# Processor.net
KiCad netlist of a schematic drawn in Altium Designer
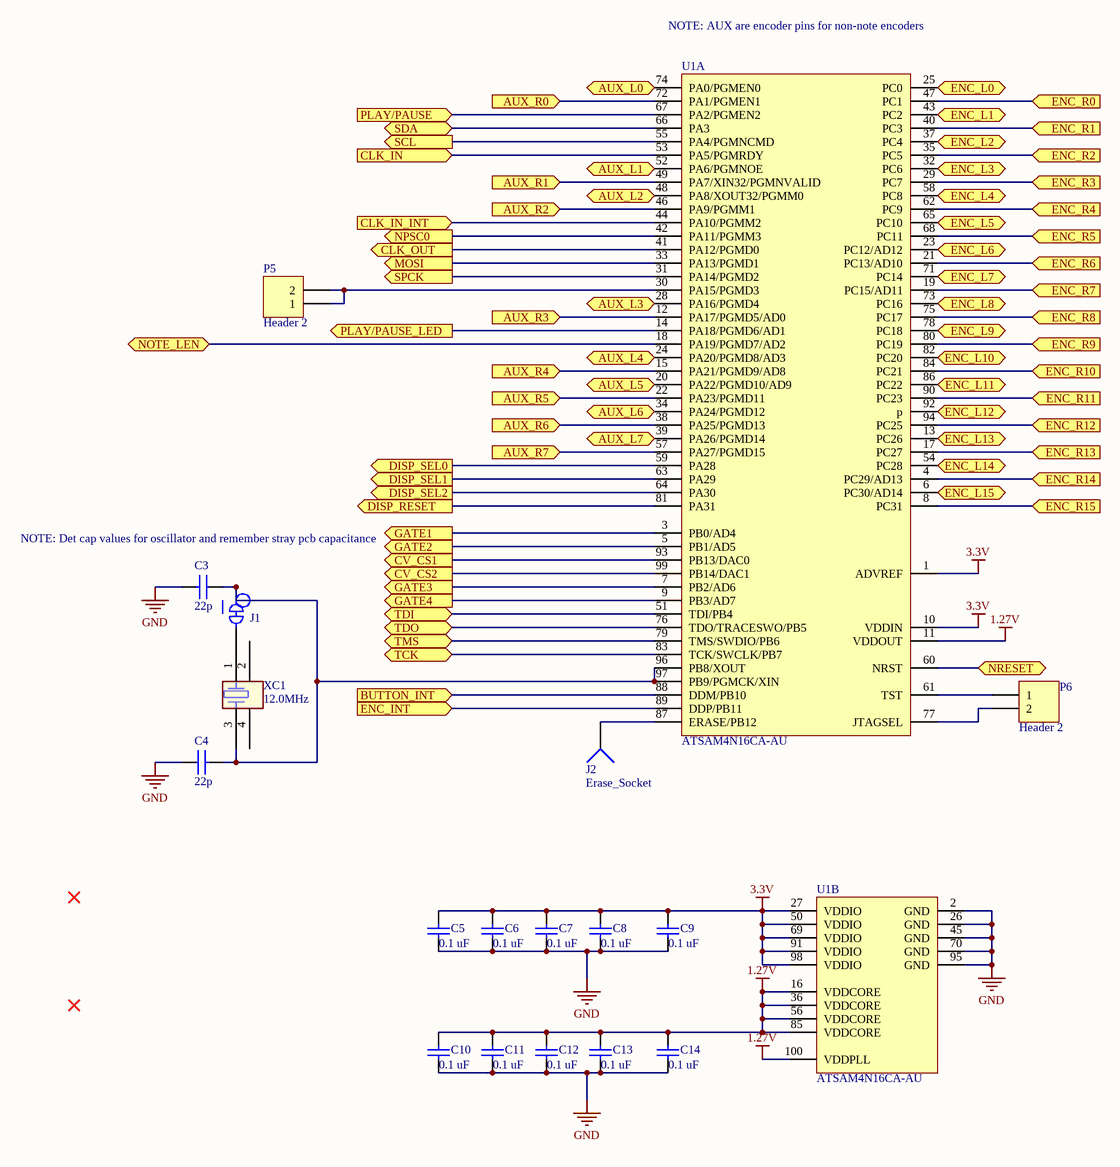
[diagram p0: Processor.SchDoc]

(export (version "E")
  (design (tool "Eeschema 10.0.6"))
  (components
    (comp (ref "C3")
      (value "22p")
      (footprint "AP1-00001")
      (description "Ceramic capacitor, SMD 0402, NP0, 50V, +/-5%")
      (fields (field (name "TOLERANCE") "50V, +/-5%") (field (name "Comment") "CAP-NONPOL"))
      (libsource (lib "AltiumDbLib") (part "CAP-NONPOL"))
    )
    (comp (ref "C4")
      (value "22p")
      (footprint "AP1-00001")
      (description "Ceramic capacitor, SMD 0402, NP0, 50V, +/-5%")
      (fields (field (name "TOLERANCE") "50V, +/-5%") (field (name "Comment") "CAP-NONPOL"))
      (libsource (lib "AltiumDbLib") (part "CAP-NONPOL"))
    )
    (comp (ref "C5")
      (value "0.1 uF")
      (footprint "C0805")
      (description "Capacitor")
      (fields (field (name "PUBLISHER") "Altium Limited"))
      (libsource (lib "Miscellaneous Devices") (part "Cap"))
    )
    (comp (ref "C6")
      (value "0.1 uF")
      (footprint "C0805")
      (description "Capacitor")
      (fields (field (name "PUBLISHER") "Altium Limited"))
      (libsource (lib "Miscellaneous Devices") (part "Cap"))
    )
    (comp (ref "C7")
      (value "0.1 uF")
      (footprint "C0805")
      (description "Capacitor")
      (fields (field (name "PUBLISHER") "Altium Limited"))
      (libsource (lib "Miscellaneous Devices") (part "Cap"))
    )
    (comp (ref "C8")
      (value "0.1 uF")
      (footprint "C0805")
      (description "Capacitor")
      (fields (field (name "PUBLISHER") "Altium Limited"))
      (libsource (lib "Miscellaneous Devices") (part "Cap"))
    )
    (comp (ref "C9")
      (value "0.1 uF")
      (footprint "C0805")
      (description "Capacitor")
      (fields (field (name "PUBLISHER") "Altium Limited"))
      (libsource (lib "Miscellaneous Devices") (part "Cap"))
    )
    (comp (ref "C10")
      (value "0.1 uF")
      (footprint "C0805")
      (description "Capacitor")
      (fields (field (name "PUBLISHER") "Altium Limited"))
      (libsource (lib "Miscellaneous Devices") (part "Cap"))
    )
    (comp (ref "C11")
      (value "0.1 uF")
      (footprint "C0805")
      (description "Capacitor")
      (fields (field (name "PUBLISHER") "Altium Limited"))
      (libsource (lib "Miscellaneous Devices") (part "Cap"))
    )
    (comp (ref "C12")
      (value "0.1 uF")
      (footprint "C0805")
      (description "Capacitor")
      (fields (field (name "PUBLISHER") "Altium Limited"))
      (libsource (lib "Miscellaneous Devices") (part "Cap"))
    )
    (comp (ref "C13")
      (value "0.1 uF")
      (footprint "C0805")
      (description "Capacitor")
      (fields (field (name "PUBLISHER") "Altium Limited"))
      (libsource (lib "Miscellaneous Devices") (part "Cap"))
    )
    (comp (ref "C14")
      (value "0.1 uF")
      (footprint "C0805")
      (description "Capacitor")
      (fields (field (name "PUBLISHER") "Altium Limited"))
      (libsource (lib "Miscellaneous Devices") (part "Cap"))
    )
    (comp (ref "J1")
      (value "SMD-STRAP_CLOSED")
      (footprint "AP9-00044")
      (description "Default closed SMD strap, 0603 size")
      (libsource (lib "AltiumDbLib") (part "SMD-STRAP_CLOSED"))
    )
    (comp (ref "J2")
      (value "Erase_Socket")
      (footprint "PIN1")
      (description "Socket")
      (fields (field (name "PUBLISHER") "Altium Limited"))
      (libsource (lib "Miscellaneous Connectors") (part "Socket"))
    )
    (comp (ref "P5")
      (value "Header 2")
      (footprint "HDR1X2")
      (description "Header, 2-Pin")
      (fields (field (name "PUBLISHER") "Altium Limited"))
      (libsource (lib "") (part "Header 2_1"))
    )
    (comp (ref "P6")
      (value "Header 2")
      (footprint "HDR1X2")
      (description "Header, 2-Pin")
      (fields (field (name "PUBLISHER") "Altium Limited"))
      (libsource (lib "Miscellaneous Connectors") (part "Header 2"))
    )
    (comp (ref "U1")
      (value "ATSAM4N16CA-AU")
      (footprint "LQFP100_N")
      (libsource (lib "Atmel Microcontroller ARM") (part "ATSAM4S16CA-AU"))
    )
    (comp (ref "XC1")
      (value "12.0MHz")
      (footprint "AP7-00039")
      (description "Fox FQ5032B 12.0MHz SMD crystal 738B-12")
      (fields (field (name "TOLERANCE") "30PPM") (field (name "MANUFACTURER") "Fox  Electronics"))
      (libsource (lib "AltiumDbLib") (part "CRYSTAL1324"))
    )
  )
  (nets
    (net (code "1") (name "/AUX_L0") (class "Default")
      (node (ref "U1") (pin "74") (pinfunction "PA0/PGMEN0_74") (pintype "passive"))
    )
    (net (code "2") (name "/AUX_L1") (class "Default")
      (node (ref "U1") (pin "52") (pinfunction "PA6/PGMNOE_52") (pintype "passive"))
    )
    (net (code "3") (name "/AUX_L2") (class "Default")
      (node (ref "U1") (pin "48") (pinfunction "PA8/XOUT32/PGMM0_48") (pintype "passive"))
    )
    (net (code "4") (name "/AUX_L3") (class "Default")
      (node (ref "U1") (pin "28") (pinfunction "PA16/PGMD4_28") (pintype "passive"))
    )
    (net (code "5") (name "/AUX_L4") (class "Default")
      (node (ref "U1") (pin "24") (pinfunction "PA20/PGMD8/AD3_24") (pintype "passive"))
    )
    (net (code "6") (name "/AUX_L5") (class "Default")
      (node (ref "U1") (pin "20") (pinfunction "PA22/PGMD10/AD9_20") (pintype "passive"))
    )
    (net (code "7") (name "/AUX_L6") (class "Default")
      (node (ref "U1") (pin "34") (pinfunction "PA24/PGMD12_34") (pintype "passive"))
    )
    (net (code "8") (name "/AUX_L7") (class "Default")
      (node (ref "U1") (pin "39") (pinfunction "PA26/PGMD14_39") (pintype "passive"))
    )
    (net (code "9") (name "/AUX_R0") (class "Default")
      (node (ref "U1") (pin "72") (pinfunction "PA1/PGMEN1_72") (pintype "passive"))
    )
    (net (code "10") (name "/AUX_R1") (class "Default")
      (node (ref "U1") (pin "49") (pinfunction "PA7/XIN32/PGMNVALID_49") (pintype "passive"))
    )
    (net (code "11") (name "/AUX_R2") (class "Default")
      (node (ref "U1") (pin "46") (pinfunction "PA9/PGMM1_46") (pintype "passive"))
    )
    (net (code "12") (name "/AUX_R3") (class "Default")
      (node (ref "U1") (pin "12") (pinfunction "PA17/PGMD5/AD0_12") (pintype "passive"))
    )
    (net (code "13") (name "/AUX_R4") (class "Default")
      (node (ref "U1") (pin "15") (pinfunction "PA21/PGMD9/AD8_15") (pintype "passive"))
    )
    (net (code "14") (name "/AUX_R5") (class "Default")
      (node (ref "U1") (pin "22") (pinfunction "PA23/PGMD11_22") (pintype "passive"))
    )
    (net (code "15") (name "/AUX_R6") (class "Default")
      (node (ref "U1") (pin "38") (pinfunction "PA25/PGMD13_38") (pintype "passive"))
    )
    (net (code "16") (name "/AUX_R7") (class "Default")
      (node (ref "U1") (pin "57") (pinfunction "PA27/PGMD15_57") (pintype "passive"))
    )
    (net (code "17") (name "/BUTTON_INT") (class "Default")
      (node (ref "U1") (pin "88") (pinfunction "DDM/PB10_88") (pintype "passive"))
    )
    (net (code "18") (name "/CLK_IN") (class "Default")
      (node (ref "U1") (pin "53") (pinfunction "PA5/PGMRDY_53") (pintype "passive"))
    )
    (net (code "19") (name "/CLK_IN_INT") (class "Default")
      (node (ref "U1") (pin "44") (pinfunction "PA10/PGMM2_44") (pintype "passive"))
    )
    (net (code "20") (name "/CLK_OUT") (class "Default")
      (node (ref "U1") (pin "41") (pinfunction "PA12/PGMD0_41") (pintype "passive"))
    )
    (net (code "21") (name "/CV_CS1") (class "Default")
      (node (ref "U1") (pin "93") (pinfunction "PB13/DAC0_93") (pintype "passive"))
    )
    (net (code "22") (name "/CV_CS2") (class "Default")
      (node (ref "U1") (pin "99") (pinfunction "PB14/DAC1_99") (pintype "passive"))
    )
    (net (code "23") (name "/DISP_RESET") (class "Default")
      (node (ref "U1") (pin "81") (pinfunction "PA31_81") (pintype "passive"))
    )
    (net (code "24") (name "/DISP_SEL0") (class "Default")
      (node (ref "U1") (pin "59") (pinfunction "PA28_59") (pintype "passive"))
    )
    (net (code "25") (name "/DISP_SEL1") (class "Default")
      (node (ref "U1") (pin "63") (pinfunction "PA29_63") (pintype "passive"))
    )
    (net (code "26") (name "/DISP_SEL2") (class "Default")
      (node (ref "U1") (pin "64") (pinfunction "PA30_64") (pintype "passive"))
    )
    (net (code "27") (name "/ENC_INT") (class "Default")
      (node (ref "U1") (pin "89") (pinfunction "DDP/PB11_89") (pintype "passive"))
    )
    (net (code "28") (name "/ENC_L0") (class "Default")
      (node (ref "U1") (pin "25") (pinfunction "PC0_25") (pintype "passive"))
    )
    (net (code "29") (name "/ENC_L1") (class "Default")
      (node (ref "U1") (pin "43") (pinfunction "PC2_43") (pintype "passive"))
    )
    (net (code "30") (name "/ENC_L2") (class "Default")
      (node (ref "U1") (pin "37") (pinfunction "PC4_37") (pintype "passive"))
    )
    (net (code "31") (name "/ENC_L3") (class "Default")
      (node (ref "U1") (pin "32") (pinfunction "PC6_32") (pintype "passive"))
    )
    (net (code "32") (name "/ENC_L4") (class "Default")
      (node (ref "U1") (pin "58") (pinfunction "PC8_58") (pintype "passive"))
    )
    (net (code "33") (name "/ENC_L5") (class "Default")
      (node (ref "U1") (pin "65") (pinfunction "PC10_65") (pintype "passive"))
    )
    (net (code "34") (name "/ENC_L6") (class "Default")
      (node (ref "U1") (pin "23") (pinfunction "PC12/AD12_23") (pintype "passive"))
    )
    (net (code "35") (name "/ENC_L7") (class "Default")
      (node (ref "U1") (pin "71") (pinfunction "PC14_71") (pintype "passive"))
    )
    (net (code "36") (name "/ENC_L8") (class "Default")
      (node (ref "U1") (pin "73") (pinfunction "PC16_73") (pintype "passive"))
    )
    (net (code "37") (name "/ENC_L9") (class "Default")
      (node (ref "U1") (pin "78") (pinfunction "PC18_78") (pintype "passive"))
    )
    (net (code "38") (name "/ENC_L10") (class "Default")
      (node (ref "U1") (pin "82") (pinfunction "PC20_82") (pintype "passive"))
    )
    (net (code "39") (name "/ENC_L11") (class "Default")
      (node (ref "U1") (pin "86") (pinfunction "PC22_86") (pintype "passive"))
    )
    (net (code "40") (name "/ENC_L12") (class "Default")
      (node (ref "U1") (pin "92") (pinfunction "p_92") (pintype "passive"))
    )
    (net (code "41") (name "/ENC_L13") (class "Default")
      (node (ref "U1") (pin "13") (pinfunction "PC26_13") (pintype "passive"))
    )
    (net (code "42") (name "/ENC_L14") (class "Default")
      (node (ref "U1") (pin "54") (pinfunction "PC28_54") (pintype "passive"))
    )
    (net (code "43") (name "/ENC_L15") (class "Default")
      (node (ref "U1") (pin "6") (pinfunction "PC30/AD14_6") (pintype "passive"))
    )
    (net (code "44") (name "/ENC_R0") (class "Default")
      (node (ref "U1") (pin "47") (pinfunction "PC1_47") (pintype "passive"))
    )
    (net (code "45") (name "/ENC_R1") (class "Default")
      (node (ref "U1") (pin "40") (pinfunction "PC3_40") (pintype "passive"))
    )
    (net (code "46") (name "/ENC_R2") (class "Default")
      (node (ref "U1") (pin "35") (pinfunction "PC5_35") (pintype "passive"))
    )
    (net (code "47") (name "/ENC_R3") (class "Default")
      (node (ref "U1") (pin "29") (pinfunction "PC7_29") (pintype "passive"))
    )
    (net (code "48") (name "/ENC_R4") (class "Default")
      (node (ref "U1") (pin "62") (pinfunction "PC9_62") (pintype "passive"))
    )
    (net (code "49") (name "/ENC_R5") (class "Default")
      (node (ref "U1") (pin "68") (pinfunction "PC11_68") (pintype "passive"))
    )
    (net (code "50") (name "/ENC_R6") (class "Default")
      (node (ref "U1") (pin "21") (pinfunction "PC13/AD10_21") (pintype "passive"))
    )
    (net (code "51") (name "/ENC_R7") (class "Default")
      (node (ref "U1") (pin "19") (pinfunction "PC15/AD11_19") (pintype "passive"))
    )
    (net (code "52") (name "/ENC_R8") (class "Default")
      (node (ref "U1") (pin "75") (pinfunction "PC17_75") (pintype "passive"))
    )
    (net (code "53") (name "/ENC_R9") (class "Default")
      (node (ref "U1") (pin "80") (pinfunction "PC19_80") (pintype "passive"))
    )
    (net (code "54") (name "/ENC_R10") (class "Default")
      (node (ref "U1") (pin "84") (pinfunction "PC21_84") (pintype "passive"))
    )
    (net (code "55") (name "/ENC_R11") (class "Default")
      (node (ref "U1") (pin "90") (pinfunction "PC23_90") (pintype "passive"))
    )
    (net (code "56") (name "/ENC_R12") (class "Default")
      (node (ref "U1") (pin "94") (pinfunction "PC25_94") (pintype "passive"))
    )
    (net (code "57") (name "/ENC_R13") (class "Default")
      (node (ref "U1") (pin "17") (pinfunction "PC27_17") (pintype "passive"))
    )
    (net (code "58") (name "/ENC_R14") (class "Default")
      (node (ref "U1") (pin "4") (pinfunction "PC29/AD13_4") (pintype "passive"))
    )
    (net (code "59") (name "/ENC_R15") (class "Default")
      (node (ref "U1") (pin "8") (pinfunction "PC31_8") (pintype "passive"))
    )
    (net (code "60") (name "/GATE1") (class "Default")
      (node (ref "U1") (pin "3") (pinfunction "PB0/AD4_3") (pintype "passive"))
    )
    (net (code "61") (name "/GATE2") (class "Default")
      (node (ref "U1") (pin "5") (pinfunction "PB1/AD5_5") (pintype "passive"))
    )
    (net (code "62") (name "/GATE3") (class "Default")
      (node (ref "U1") (pin "7") (pinfunction "PB2/AD6_7") (pintype "passive"))
    )
    (net (code "63") (name "/GATE4") (class "Default")
      (node (ref "U1") (pin "9") (pinfunction "PB3/AD7_9") (pintype "passive"))
    )
    (net (code "64") (name "/MOSI") (class "Default")
      (node (ref "U1") (pin "33") (pinfunction "PA13/PGMD1_33") (pintype "passive"))
    )
    (net (code "65") (name "/NOTE_LEN") (class "Default")
      (node (ref "U1") (pin "18") (pinfunction "PA19/PGMD7/AD2_18") (pintype "passive"))
    )
    (net (code "66") (name "/NPSC0") (class "Default")
      (node (ref "U1") (pin "42") (pinfunction "PA11/PGMM3_42") (pintype "passive"))
    )
    (net (code "67") (name "/NRESET") (class "Default")
      (node (ref "U1") (pin "60") (pinfunction "NRST_60") (pintype "passive"))
    )
    (net (code "68") (name "/PLAY{slash}PAUSE") (class "Default")
      (node (ref "U1") (pin "67") (pinfunction "PA2/PGMEN2_67") (pintype "passive"))
    )
    (net (code "69") (name "/PLAY{slash}PAUSE_LED") (class "Default")
      (node (ref "U1") (pin "14") (pinfunction "PA18/PGMD6/AD1_14") (pintype "passive"))
    )
    (net (code "70") (name "/SCL") (class "Default")
      (node (ref "U1") (pin "55") (pinfunction "PA4/PGMNCMD_55") (pintype "passive"))
    )
    (net (code "71") (name "/SDA") (class "Default")
      (node (ref "U1") (pin "66") (pinfunction "PA3_66") (pintype "passive"))
    )
    (net (code "72") (name "/SPCK") (class "Default")
      (node (ref "U1") (pin "31") (pinfunction "PA14/PGMD2_31") (pintype "passive"))
    )
    (net (code "73") (name "/TCK") (class "Default")
      (node (ref "U1") (pin "83") (pinfunction "TCK/SWCLK/PB7_83") (pintype "passive"))
    )
    (net (code "74") (name "/TDI") (class "Default")
      (node (ref "U1") (pin "51") (pinfunction "TDI/PB4_51") (pintype "passive"))
    )
    (net (code "75") (name "/TDO") (class "Default")
      (node (ref "U1") (pin "76") (pinfunction "TDO/TRACESWO/PB5_76") (pintype "passive"))
    )
    (net (code "76") (name "/TMS") (class "Default")
      (node (ref "U1") (pin "79") (pinfunction "TMS/SWDIO/PB6_79") (pintype "passive"))
    )
    (net (code "77") (name "1.27V") (class "Default")
      (node (ref "C10") (pin "2") (pinfunction "2_2") (pintype "passive"))
      (node (ref "C11") (pin "2") (pinfunction "2_2") (pintype "passive"))
      (node (ref "C12") (pin "2") (pinfunction "2_2") (pintype "passive"))
      (node (ref "C13") (pin "2") (pinfunction "2_2") (pintype "passive"))
      (node (ref "C14") (pin "2") (pinfunction "2_2") (pintype "passive"))
      (node (ref "U1") (pin "100") (pinfunction "VDDPLL_100") (pintype "power_in"))
      (node (ref "U1") (pin "11") (pinfunction "VDDOUT_11") (pintype "power_in"))
      (node (ref "U1") (pin "16") (pinfunction "VDDCORE_16") (pintype "power_in"))
      (node (ref "U1") (pin "36") (pinfunction "VDDCORE_36") (pintype "power_in"))
      (node (ref "U1") (pin "56") (pinfunction "VDDCORE_56") (pintype "power_in"))
      (node (ref "U1") (pin "85") (pinfunction "VDDCORE_85") (pintype "power_in"))
    )
    (net (code "78") (name "3.3V") (class "Default")
      (node (ref "C5") (pin "2") (pinfunction "2_2") (pintype "passive"))
      (node (ref "C6") (pin "2") (pinfunction "2_2") (pintype "passive"))
      (node (ref "C7") (pin "2") (pinfunction "2_2") (pintype "passive"))
      (node (ref "C8") (pin "2") (pinfunction "2_2") (pintype "passive"))
      (node (ref "C9") (pin "2") (pinfunction "2_2") (pintype "passive"))
      (node (ref "U1") (pin "1") (pinfunction "ADVREF_1") (pintype "passive"))
      (node (ref "U1") (pin "10") (pinfunction "VDDIN_10") (pintype "power_in"))
      (node (ref "U1") (pin "27") (pinfunction "VDDIO_27") (pintype "power_in"))
      (node (ref "U1") (pin "50") (pinfunction "VDDIO_50") (pintype "power_in"))
      (node (ref "U1") (pin "69") (pinfunction "VDDIO_69") (pintype "power_in"))
      (node (ref "U1") (pin "91") (pinfunction "VDDIO_91") (pintype "power_in"))
      (node (ref "U1") (pin "98") (pinfunction "VDDIO_98") (pintype "power_in"))
    )
    (net (code "79") (name "GND") (class "Default")
      (node (ref "C10") (pin "1") (pinfunction "1_1") (pintype "passive"))
      (node (ref "C11") (pin "1") (pinfunction "1_1") (pintype "passive"))
      (node (ref "C12") (pin "1") (pinfunction "1_1") (pintype "passive"))
      (node (ref "C13") (pin "1") (pinfunction "1_1") (pintype "passive"))
      (node (ref "C14") (pin "1") (pinfunction "1_1") (pintype "passive"))
      (node (ref "C3") (pin "2") (pinfunction "2_2") (pintype "passive"))
      (node (ref "C4") (pin "1") (pinfunction "1_1") (pintype "passive"))
      (node (ref "C5") (pin "1") (pinfunction "1_1") (pintype "passive"))
      (node (ref "C6") (pin "1") (pinfunction "1_1") (pintype "passive"))
      (node (ref "C7") (pin "1") (pinfunction "1_1") (pintype "passive"))
      (node (ref "C8") (pin "1") (pinfunction "1_1") (pintype "passive"))
      (node (ref "C9") (pin "1") (pinfunction "1_1") (pintype "passive"))
      (node (ref "U1") (pin "2") (pinfunction "GND_2") (pintype "power_in"))
      (node (ref "U1") (pin "26") (pinfunction "GND_26") (pintype "power_in"))
      (node (ref "U1") (pin "45") (pinfunction "GND_45") (pintype "power_in"))
      (node (ref "U1") (pin "70") (pinfunction "GND_70") (pintype "power_in"))
      (node (ref "U1") (pin "95") (pinfunction "GND_95") (pintype "power_in"))
    )
    (net (code "80") (name "Net-(J1-Pad2)") (class "Default")
      (node (ref "J1") (pin "2") (pinfunction "2_2") (pintype "passive"))
      (node (ref "XC1") (pin "1") (pinfunction "1_1") (pintype "passive"))
    )
    (net (code "81") (name "Net-(U1A-ERASE{slash}PB12)") (class "Default")
      (node (ref "J2") (pin "1") (pinfunction "1_1") (pintype "passive"))
      (node (ref "U1") (pin "87") (pinfunction "ERASE/PB12_87") (pintype "passive"))
    )
    (net (code "82") (name "Net-(U1A-JTAGSEL)") (class "Default")
      (node (ref "P6") (pin "2") (pinfunction "2_2") (pintype "passive"))
      (node (ref "U1") (pin "77") (pinfunction "JTAGSEL_77") (pintype "passive"))
    )
    (net (code "83") (name "Net-(U1A-PA15{slash}PGMD3)") (class "Default")
      (node (ref "P5") (pin "1") (pinfunction "1_1") (pintype "passive"))
      (node (ref "P5") (pin "2") (pinfunction "2_2") (pintype "passive"))
      (node (ref "U1") (pin "30") (pinfunction "PA15/PGMD3_30") (pintype "passive"))
    )
    (net (code "84") (name "Net-(U1A-PB8{slash}XOUT)") (class "Default")
      (node (ref "C3") (pin "1") (pinfunction "1_1") (pintype "passive"))
      (node (ref "C4") (pin "2") (pinfunction "2_2") (pintype "passive"))
      (node (ref "J1") (pin "1") (pinfunction "1_1") (pintype "passive"))
      (node (ref "U1") (pin "96") (pinfunction "PB8/XOUT_96") (pintype "passive"))
      (node (ref "U1") (pin "97") (pinfunction "PB9/PGMCK/XIN_97") (pintype "passive"))
      (node (ref "XC1") (pin "3") (pinfunction "3_3") (pintype "passive"))
    )
    (net (code "85") (name "Net-(U1A-TST)") (class "Default")
      (node (ref "P6") (pin "1") (pinfunction "1_1") (pintype "passive"))
      (node (ref "U1") (pin "61") (pinfunction "TST_61") (pintype "passive"))
    )
    (net (code "86") (name "unconnected-(XC1-Pad2)") (class "Default")
      (node (ref "XC1") (pin "2") (pinfunction "2_2") (pintype "passive"))
    )
    (net (code "87") (name "unconnected-(XC1-Pad4)") (class "Default")
      (node (ref "XC1") (pin "4") (pinfunction "4_4") (pintype "passive"))
    )
  )
)
